# openSX70_MEROE_V7-5_20190606.net
KiCad netlist of a schematic drawn in EAGLE
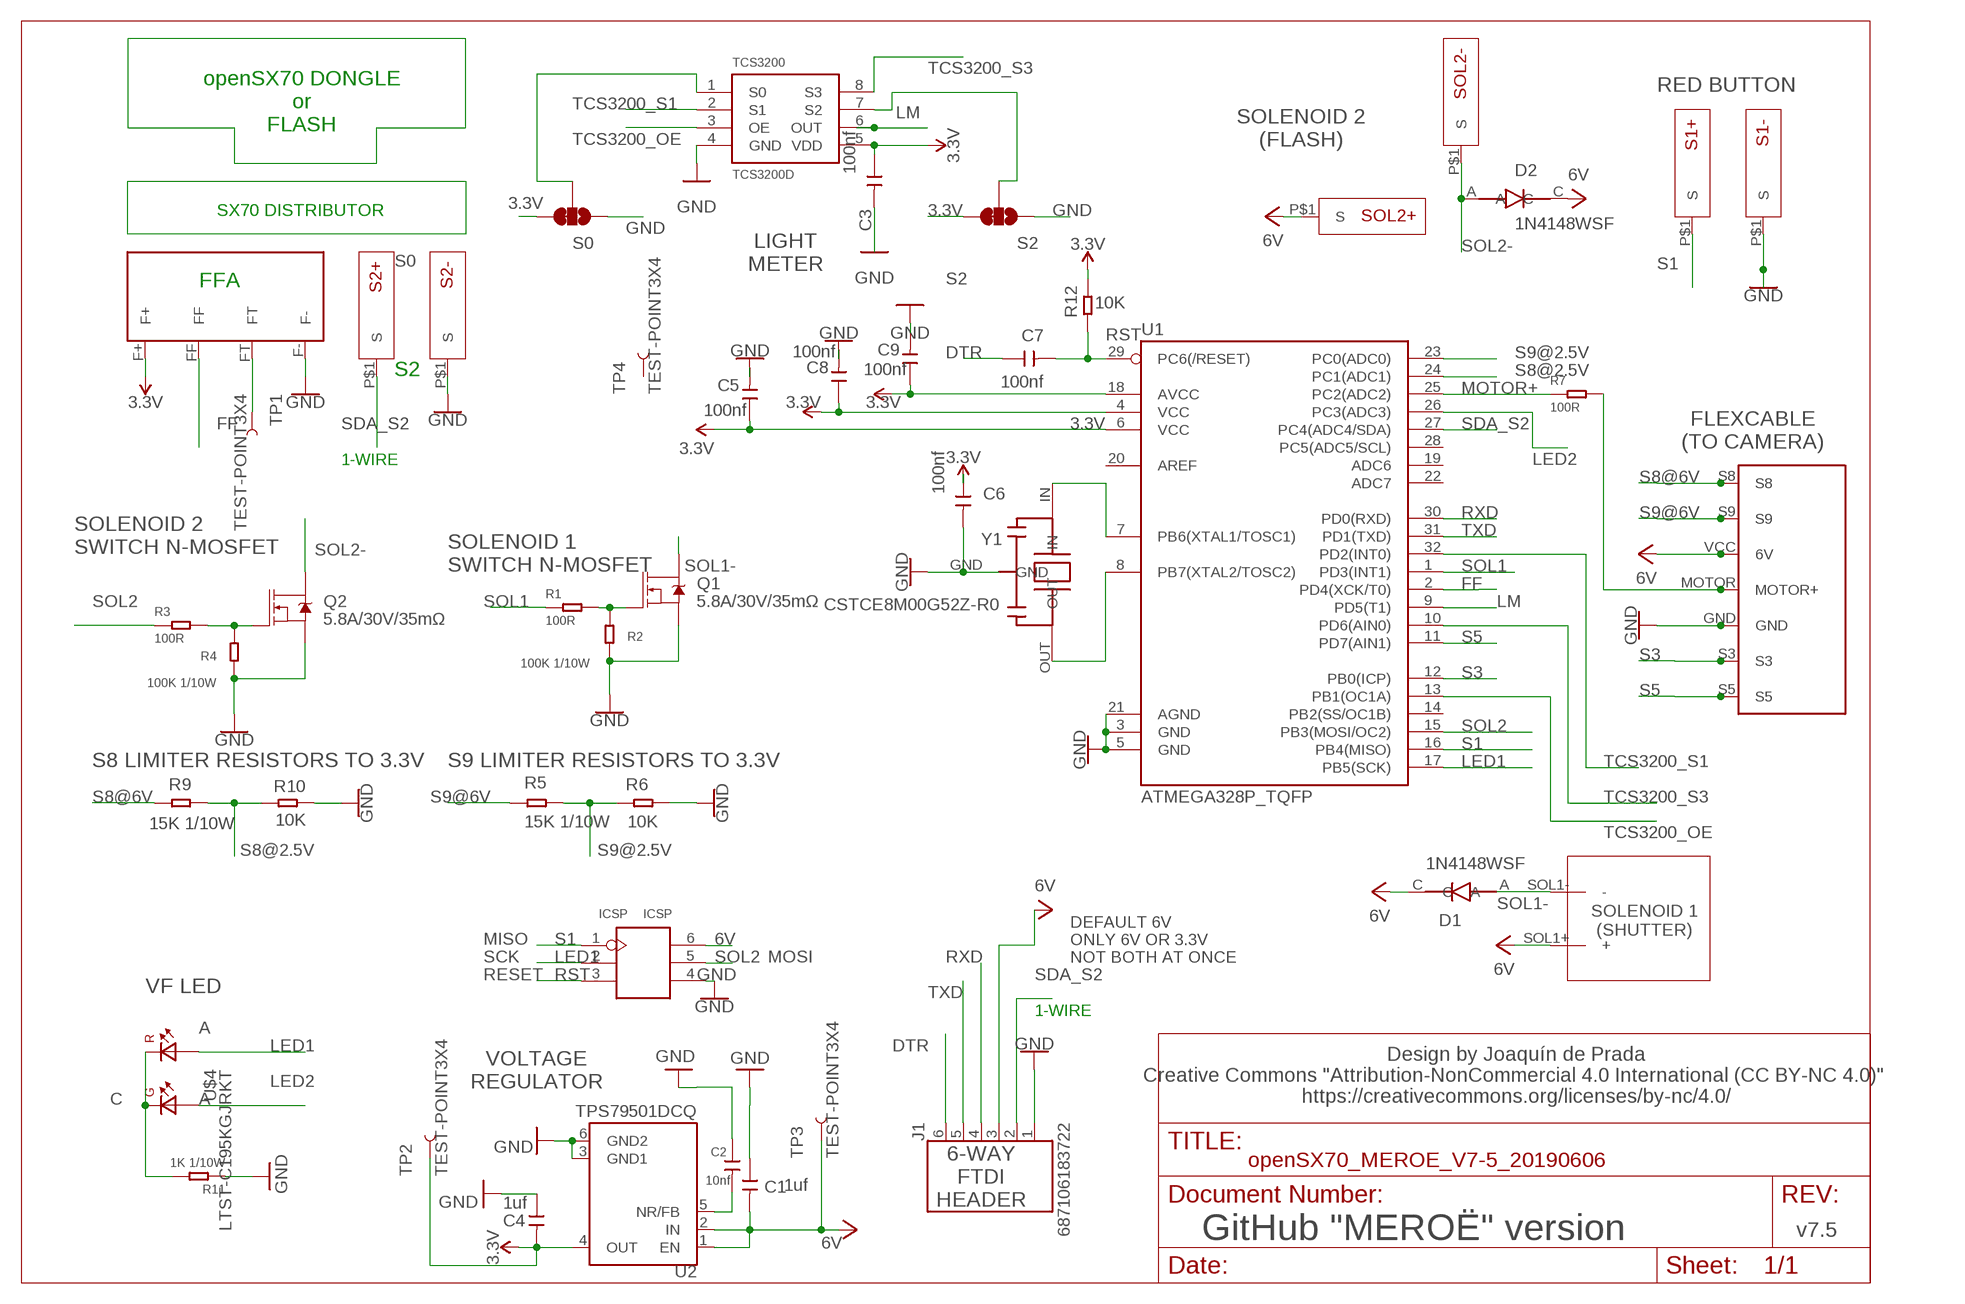
[diagram p0: schematic, sheet 1]

(export (version "E")
  (design (tool "Eeschema 10.0.6"))
  (components
    (comp (ref "C1")
      (value "1uf")
      (footprint "eagle-import:C0603")
      (fields (field (name "MPN") "CC0603KRX5R6BB106"))
      (libsource (lib "eagle-import") (part "CERAMIC-10UF-10V-10%-X5R(0603)"))
    )
    (comp (ref "C2")
      (value "10nf")
      (footprint "eagle-import:C0603")
      (fields (field (name "MPN") "CC0603KRX7R9BB104"))
      (libsource (lib "eagle-import") (part "CERAMIC-100NF-50V-10%-X7R(0603)"))
    )
    (comp (ref "C3")
      (value "100nf")
      (footprint "eagle-import:C0603")
      (fields (field (name "MPN") "CC0603KRX7R9BB104"))
      (libsource (lib "eagle-import") (part "CERAMIC-100NF-50V-10%-X7R(0603)"))
    )
    (comp (ref "C4")
      (value "1uf")
      (footprint "eagle-import:C0603")
      (fields (field (name "MPN") "CC0603KRX5R6BB106"))
      (libsource (lib "eagle-import") (part "CERAMIC-10UF-10V-10%-X5R(0603)"))
    )
    (comp (ref "C5")
      (value "100nf")
      (footprint "eagle-import:C0603")
      (fields (field (name "MPN") "CC0603KRX7R9BB104"))
      (libsource (lib "eagle-import") (part "CERAMIC-100NF-50V-10%-X7R(0603)"))
    )
    (comp (ref "C6")
      (value "100nf")
      (footprint "eagle-import:C0603")
      (fields (field (name "MPN") "CC0603KRX7R9BB104"))
      (libsource (lib "eagle-import") (part "CERAMIC-100NF-50V-10%-X7R(0603)"))
    )
    (comp (ref "C7")
      (value "100nf")
      (footprint "eagle-import:C0603")
      (fields (field (name "MPN") "CC0603KRX7R9BB104"))
      (libsource (lib "eagle-import") (part "CERAMIC-100NF-50V-10%-X7R(0603)"))
    )
    (comp (ref "C8")
      (value "100nf")
      (footprint "eagle-import:C0603")
      (fields (field (name "MPN") "CC0603KRX7R9BB104"))
      (libsource (lib "eagle-import") (part "CERAMIC-100NF-50V-10%-X7R(0603)"))
    )
    (comp (ref "C9")
      (value "100nf")
      (footprint "eagle-import:C0603")
      (fields (field (name "MPN") "CC0603KRX7R9BB104"))
      (libsource (lib "eagle-import") (part "CERAMIC-100NF-50V-10%-X7R(0603)"))
    )
    (comp (ref "D1")
      (value "1N4148WSF")
      (footprint "eagle-import:SODFL2512X100N")
      (fields (field (name "MANUFACTURER") "Fairchild Semiconductor"))
      (libsource (lib "eagle-import") (part "1N4148WS"))
    )
    (comp (ref "D2")
      (value "1N4148WSF")
      (footprint "eagle-import:SODFL2512X100N")
      (fields (field (name "MANUFACTURER") "Fairchild Semiconductor"))
      (libsource (lib "eagle-import") (part "1N4148WS"))
    )
    (comp (ref "ICSP")
      (value "ICSP")
      (footprint "eagle-import:H2X3-2.54")
      (libsource (lib "eagle-import") (part "ICSP"))
    )
    (comp (ref "J1")
      (value "687106183722")
      (footprint "eagle-import:687106183722")
      (fields (field (name "MF") "Wurth Electronics"))
      (libsource (lib "eagle-import") (part "687106183722"))
    )
    (comp (ref "Q1")
      (value "5.8A/30V/35mΩ")
      (footprint "eagle-import:SOT23-3")
      (libsource (lib "eagle-import") (part "MOSFET-NCH-AO3404A"))
    )
    (comp (ref "Q2")
      (value "5.8A/30V/35mΩ")
      (footprint "eagle-import:SOT23-3")
      (libsource (lib "eagle-import") (part "MOSFET-NCH-AO3404A"))
    )
    (comp (ref "R1")
      (value "100R")
      (footprint "eagle-import:R0603")
      (fields (field (name "MPN") "RC0603JR-07100RL"))
      (libsource (lib "eagle-import") (part "SMD-RES-100R-5%-1/10W(0603)"))
    )
    (comp (ref "R2")
      (value "100K 1/10W")
      (footprint "eagle-import:R0603")
      (fields (field (name "MPN") "RC0603JR-07100KL"))
      (libsource (lib "eagle-import") (part "SMD-RES-100K-5%-1/10W(0603)"))
    )
    (comp (ref "R3")
      (value "100R")
      (footprint "eagle-import:R0603")
      (fields (field (name "MPN") "RC0603JR-07100RL"))
      (libsource (lib "eagle-import") (part "SMD-RES-100R-5%-1/10W(0603)"))
    )
    (comp (ref "R4")
      (value "100K 1/10W")
      (footprint "eagle-import:R0603")
      (fields (field (name "MPN") "RC0603JR-07100KL"))
      (libsource (lib "eagle-import") (part "SMD-RES-100K-5%-1/10W(0603)"))
    )
    (comp (ref "R5")
      (value "15K 1/10W")
      (footprint "eagle-import:R0603")
      (fields (field (name "MPN") "RC0603FR-0715KL"))
      (libsource (lib "eagle-import") (part "SMD-RES-15K-1%-1/10W(0603)"))
    )
    (comp (ref "R6")
      (value "10K")
      (footprint "eagle-import:R0603")
      (fields (field (name "MPN") "RC0603FR-0710KL"))
      (libsource (lib "eagle-import") (part "SMD-RES-10K-1%-1/10W(0603)"))
    )
    (comp (ref "R7")
      (value "100R")
      (footprint "eagle-import:R0603")
      (fields (field (name "MPN") "RC0603JR-07100RL"))
      (libsource (lib "eagle-import") (part "SMD-RES-100R-5%-1/10W(0603)"))
    )
    (comp (ref "R9")
      (value "15K 1/10W")
      (footprint "eagle-import:R0603")
      (fields (field (name "MPN") "RC0603FR-0715KL"))
      (libsource (lib "eagle-import") (part "SMD-RES-15K-1%-1/10W(0603)"))
    )
    (comp (ref "R10")
      (value "10K")
      (footprint "eagle-import:R0603")
      (fields (field (name "MPN") "RC0603FR-0710KL"))
      (libsource (lib "eagle-import") (part "SMD-RES-10K-1%-1/10W(0603)"))
    )
    (comp (ref "R11")
      (value "1K 1/10W")
      (footprint "eagle-import:R0603")
      (fields (field (name "MPN") "RC0603JR-071KL"))
      (libsource (lib "eagle-import") (part "SMD-RES-1K-5%-1/10W(0603)"))
    )
    (comp (ref "R12")
      (value "10K")
      (footprint "eagle-import:R0603")
      (fields (field (name "MPN") "RC0603FR-0710KL"))
      (libsource (lib "eagle-import") (part "SMD-RES-10K-1%-1/10W(0603)"))
    )
    (comp (ref "S0")
      (value "S0")
      (footprint "eagle-import:SMT-JUMPER_3_1-NC_TRACE_SILK")
      (libsource (lib "eagle-import") (part "JUMPER-SMT_3_1-NC_TRACE_SILK"))
    )
    (comp (ref "S1+")
      (value "SX70-S-PAD-NEW")
      (footprint "eagle-import:SX70-S-PAD2")
      (libsource (lib "eagle-import") (part "SX70-S-PAD-NEW"))
    )
    (comp (ref "S1-")
      (value "SX70-S-PAD-NEW")
      (footprint "eagle-import:SX70-S-PAD2")
      (libsource (lib "eagle-import") (part "SX70-S-PAD-NEW"))
    )
    (comp (ref "S2")
      (value "S2")
      (footprint "eagle-import:SMT-JUMPER_3_1-NC_TRACE_SILK")
      (libsource (lib "eagle-import") (part "JUMPER-SMT_3_1-NC_TRACE_SILK"))
    )
    (comp (ref "S2+")
      (value "SX70-S-PAD-NEW")
      (footprint "eagle-import:SX70-S-PAD2")
      (libsource (lib "eagle-import") (part "SX70-S-PAD-NEW"))
    )
    (comp (ref "S2-")
      (value "SX70-S-PAD-NEW")
      (footprint "eagle-import:SX70-S-PAD2")
      (libsource (lib "eagle-import") (part "SX70-S-PAD-NEW"))
    )
    (comp (ref "SOL1")
      (value "SX70-SOLENOID1-2PADS")
      (footprint "eagle-import:SX70-SOLENOID1-2")
      (libsource (lib "eagle-import") (part "SX70-SOLENOID1-2PADS"))
    )
    (comp (ref "SOL2+")
      (value "SX70-S-PAD-NEW")
      (footprint "eagle-import:SX70-S-PAD2")
      (libsource (lib "eagle-import") (part "SX70-S-PAD-NEW"))
    )
    (comp (ref "SOL2-")
      (value "SX70-S-PAD-NEW")
      (footprint "eagle-import:SX70-S-PAD2")
      (libsource (lib "eagle-import") (part "SX70-S-PAD-NEW"))
    )
    (comp (ref "TCS3200")
      (value "TCS3200D")
      (footprint "eagle-import:SOIC8")
      (fields (field (name "MF") "ams") (field (name "MP") "TCS3200D-TR"))
      (libsource (lib "eagle-import") (part "TCS3200D"))
    )
    (comp (ref "TP1")
      (value "TEST-POINT3X4")
      (footprint "eagle-import:PAD.03X.04")
      (libsource (lib "eagle-import") (part "TEST-POINT3X4"))
    )
    (comp (ref "TP2")
      (value "TEST-POINT3X4")
      (footprint "eagle-import:PAD.03X.04")
      (libsource (lib "eagle-import") (part "TEST-POINT3X4"))
    )
    (comp (ref "TP3")
      (value "TEST-POINT3X4")
      (footprint "eagle-import:PAD.03X.04")
      (libsource (lib "eagle-import") (part "TEST-POINT3X4"))
    )
    (comp (ref "TP4")
      (value "TEST-POINT3X4")
      (footprint "eagle-import:PAD.03X.04")
      (libsource (lib "eagle-import") (part "TEST-POINT3X4"))
    )
    (comp (ref "U$1")
      (value "SX70-7-PAD")
      (footprint "eagle-import:SX70-7-PAD-PROPER")
      (libsource (lib "eagle-import") (part "SX70-7-PAD"))
    )
    (comp (ref "U$2")
      (value "FFA")
      (footprint "eagle-import:FFA-PAD-PACKAGE")
      (libsource (lib "eagle-import") (part "SX70-FFA-PAD"))
    )
    (comp (ref "U$4")
      (value "LTST-C195KGJRKT")
      (footprint "eagle-import:LTST-BILED-15X16")
      (fields (field (name "MF") "Lite-On Inc."))
      (libsource (lib "eagle-import") (part "LTST-C195KGJRKT"))
    )
    (comp (ref "U1")
      (value "ATMEGA328P_TQFP")
      (footprint "eagle-import:TQFP32-08")
      (libsource (lib "eagle-import") (part "ATMEGA328P_TQFP"))
    )
    (comp (ref "U2")
      (value "TPS79501DCQ")
      (footprint "eagle-import:SOT127P706X180-6N")
      (fields (field (name "MF") "Texas Instruments"))
      (libsource (lib "eagle-import") (part "TPS79501DCQ"))
    )
    (comp (ref "Y1")
      (value "CSTCE8M00G52Z-R0")
      (footprint "eagle-import:CFP95P160X100-3N")
      (fields (field (name "MF") "Murata") (field (name "MP") "CSTCE16M0V53-R0"))
      (libsource (lib "eagle-import") (part "CSTCE16M0V53-R0"))
    )
  )
  (nets
    (net (code "1") (name "/DTR") (class "Default")
      (node (ref "C7") (pin "1") (pinfunction "1_1") (pintype "passive"))
      (node (ref "J1") (pin "6") (pinfunction "1_6") (pintype "passive"))
    )
    (net (code "2") (name "/FF") (class "Default")
      (node (ref "U$2") (pin "FF") (pinfunction "FF_FF") (pintype "bidirectional"))
      (node (ref "U1") (pin "2") (pinfunction "PD4(XCK/T0)_2") (pintype "bidirectional"))
    )
    (net (code "3") (name "/LED1") (class "Default")
      (node (ref "ICSP") (pin "2") (pinfunction "SCK_2") (pintype "bidirectional"))
      (node (ref "U$4") (pin "P$2") (pinfunction "A2_P$2") (pintype "passive"))
      (node (ref "U1") (pin "17") (pinfunction "PB5(SCK)_17") (pintype "bidirectional"))
    )
    (net (code "4") (name "/LED2") (class "Default")
      (node (ref "U$4") (pin "P$1") (pinfunction "A1_P$1") (pintype "passive"))
      (node (ref "U1") (pin "26") (pinfunction "PC3(ADC3)_26") (pintype "bidirectional"))
    )
    (net (code "5") (name "/LM") (class "Default")
      (node (ref "TCS3200") (pin "6") (pinfunction "OUT_6") (pintype "bidirectional"))
      (node (ref "U1") (pin "9") (pinfunction "PD5(T1)_9") (pintype "bidirectional"))
    )
    (net (code "6") (name "/MOTOR+") (class "Default")
      (node (ref "R7") (pin "1") (pinfunction "1_1") (pintype "passive"))
      (node (ref "U1") (pin "25") (pinfunction "PC2(ADC2)_25") (pintype "bidirectional"))
    )
    (net (code "7") (name "/RST") (class "Default")
      (node (ref "C7") (pin "2") (pinfunction "2_2") (pintype "passive"))
      (node (ref "ICSP") (pin "3") (pinfunction "RST_3") (pintype "bidirectional"))
      (node (ref "R12") (pin "1") (pinfunction "1_1") (pintype "passive"))
      (node (ref "U1") (pin "29") (pinfunction "PC6(/RESET)_29") (pintype "bidirectional"))
    )
    (net (code "8") (name "/RXD") (class "Default")
      (node (ref "J1") (pin "4") (pinfunction "3_4") (pintype "passive"))
      (node (ref "U1") (pin "30") (pinfunction "PD0(RXD)_30") (pintype "bidirectional"))
    )
    (net (code "9") (name "/S1") (class "Default")
      (node (ref "ICSP") (pin "1") (pinfunction "MISO_1") (pintype "bidirectional"))
      (node (ref "S1+") (pin "P$1") (pinfunction "S_P$1") (pintype "bidirectional"))
      (node (ref "U1") (pin "16") (pinfunction "PB4(MISO)_16") (pintype "bidirectional"))
    )
    (net (code "10") (name "/S3") (class "Default")
      (node (ref "U$1") (pin "S3") (pinfunction "S3_S3") (pintype "bidirectional"))
      (node (ref "U1") (pin "12") (pinfunction "PB0(ICP)_12") (pintype "bidirectional"))
    )
    (net (code "11") (name "/S5") (class "Default")
      (node (ref "U$1") (pin "S5") (pinfunction "S5_S5") (pintype "bidirectional"))
      (node (ref "U1") (pin "11") (pinfunction "PD7(AIN1)_11") (pintype "bidirectional"))
    )
    (net (code "12") (name "/S8@2.5V") (class "Default")
      (node (ref "R10") (pin "1") (pinfunction "1_1") (pintype "passive"))
      (node (ref "R9") (pin "2") (pinfunction "2_2") (pintype "passive"))
      (node (ref "U1") (pin "24") (pinfunction "PC1(ADC1)_24") (pintype "bidirectional"))
    )
    (net (code "13") (name "/S8@6V") (class "Default")
      (node (ref "R9") (pin "1") (pinfunction "1_1") (pintype "passive"))
      (node (ref "U$1") (pin "S8") (pinfunction "S8_S8") (pintype "bidirectional"))
    )
    (net (code "14") (name "/S9@2.5V") (class "Default")
      (node (ref "R5") (pin "2") (pinfunction "2_2") (pintype "passive"))
      (node (ref "R6") (pin "1") (pinfunction "1_1") (pintype "passive"))
      (node (ref "U1") (pin "23") (pinfunction "PC0(ADC0)_23") (pintype "bidirectional"))
    )
    (net (code "15") (name "/S9@6V") (class "Default")
      (node (ref "R5") (pin "1") (pinfunction "1_1") (pintype "passive"))
      (node (ref "U$1") (pin "S9") (pinfunction "S9_S9") (pintype "bidirectional"))
    )
    (net (code "16") (name "/SDA_S2") (class "Default")
      (node (ref "J1") (pin "2") (pinfunction "5_2") (pintype "passive"))
      (node (ref "S2+") (pin "P$1") (pinfunction "S_P$1") (pintype "bidirectional"))
      (node (ref "U1") (pin "27") (pinfunction "PC4(ADC4/SDA)_27") (pintype "bidirectional"))
    )
    (net (code "17") (name "/SOL1") (class "Default")
      (node (ref "R1") (pin "1") (pinfunction "1_1") (pintype "passive"))
      (node (ref "U1") (pin "1") (pinfunction "PD3(INT1)_1") (pintype "bidirectional"))
    )
    (net (code "18") (name "/SOL1-") (class "Default")
      (node (ref "D1") (pin "A") (pinfunction "A_A") (pintype "passive"))
      (node (ref "Q1") (pin "3") (pinfunction "D_3") (pintype "bidirectional"))
      (node (ref "SOL1") (pin "SOL1-") (pinfunction "-_SOL1-") (pintype "bidirectional"))
    )
    (net (code "19") (name "/SOL2") (class "Default")
      (node (ref "ICSP") (pin "5") (pinfunction "MOSI_5") (pintype "bidirectional"))
      (node (ref "R3") (pin "1") (pinfunction "1_1") (pintype "passive"))
      (node (ref "U1") (pin "15") (pinfunction "PB3(MOSI/OC2)_15") (pintype "bidirectional"))
    )
    (net (code "20") (name "/SOL2-") (class "Default")
      (node (ref "D2") (pin "A") (pinfunction "A_A") (pintype "passive"))
      (node (ref "Q2") (pin "3") (pinfunction "D_3") (pintype "bidirectional"))
      (node (ref "SOL2-") (pin "P$1") (pinfunction "S_P$1") (pintype "bidirectional"))
    )
    (net (code "21") (name "/TCS3200_OE") (class "Default")
      (node (ref "TCS3200") (pin "3") (pinfunction "OE_3") (pintype "bidirectional"))
      (node (ref "U1") (pin "13") (pinfunction "PB1(OC1A)_13") (pintype "bidirectional"))
    )
    (net (code "22") (name "/TCS3200_S1") (class "Default")
      (node (ref "TCS3200") (pin "2") (pinfunction "S1_2") (pintype "bidirectional"))
      (node (ref "U1") (pin "32") (pinfunction "PD2(INT0)_32") (pintype "bidirectional"))
    )
    (net (code "23") (name "/TCS3200_S3") (class "Default")
      (node (ref "TCS3200") (pin "8") (pinfunction "S3_8") (pintype "bidirectional"))
      (node (ref "U1") (pin "10") (pinfunction "PD6(AIN0)_10") (pintype "bidirectional"))
    )
    (net (code "24") (name "/TXD") (class "Default")
      (node (ref "J1") (pin "5") (pinfunction "2_5") (pintype "passive"))
      (node (ref "U1") (pin "31") (pinfunction "PD1(TXD)_31") (pintype "bidirectional"))
    )
    (net (code "25") (name "3.3V") (class "Default")
      (node (ref "C3") (pin "1") (pinfunction "1_1") (pintype "passive"))
      (node (ref "C4") (pin "2") (pinfunction "2_2") (pintype "passive"))
      (node (ref "C5") (pin "1") (pinfunction "1_1") (pintype "passive"))
      (node (ref "C6") (pin "1") (pinfunction "1_1") (pintype "passive"))
      (node (ref "C8") (pin "1") (pinfunction "1_1") (pintype "passive"))
      (node (ref "C9") (pin "1") (pinfunction "1_1") (pintype "passive"))
      (node (ref "R12") (pin "2") (pinfunction "2_2") (pintype "passive"))
      (node (ref "S0") (pin "3") (pinfunction "3_3") (pintype "passive"))
      (node (ref "S2") (pin "3") (pinfunction "3_3") (pintype "passive"))
      (node (ref "TCS3200") (pin "5") (pinfunction "VDD_5") (pintype "bidirectional"))
      (node (ref "TP2") (pin "P$1") (pinfunction "1_P$1") (pintype "bidirectional"))
      (node (ref "U$2") (pin "F+") (pinfunction "F+_F+") (pintype "bidirectional"))
      (node (ref "U1") (pin "18") (pinfunction "AVCC_18") (pintype "bidirectional"))
      (node (ref "U1") (pin "4") (pinfunction "VCC_4") (pintype "bidirectional"))
      (node (ref "U1") (pin "6") (pinfunction "VCC_6") (pintype "bidirectional"))
      (node (ref "U2") (pin "4") (pinfunction "OUT_4") (pintype "output"))
    )
    (net (code "26") (name "6V") (class "Default")
      (node (ref "C1") (pin "2") (pinfunction "2_2") (pintype "passive"))
      (node (ref "D1") (pin "C") (pinfunction "C_C") (pintype "passive"))
      (node (ref "D2") (pin "C") (pinfunction "C_C") (pintype "passive"))
      (node (ref "ICSP") (pin "6") (pinfunction "VCC_6") (pintype "bidirectional"))
      (node (ref "J1") (pin "3") (pinfunction "4_3") (pintype "passive"))
      (node (ref "SOL1") (pin "SOL1+") (pinfunction "+_SOL1+") (pintype "bidirectional"))
      (node (ref "SOL2+") (pin "P$1") (pinfunction "S_P$1") (pintype "bidirectional"))
      (node (ref "TP3") (pin "P$1") (pinfunction "1_P$1") (pintype "bidirectional"))
      (node (ref "U$1") (pin "VCC") (pinfunction "6V_VCC") (pintype "bidirectional"))
      (node (ref "U2") (pin "1") (pinfunction "EN_1") (pintype "input"))
      (node (ref "U2") (pin "2") (pinfunction "IN_2") (pintype "input"))
    )
    (net (code "27") (name "GND") (class "Default")
      (node (ref "C1") (pin "1") (pinfunction "1_1") (pintype "passive"))
      (node (ref "C2") (pin "1") (pinfunction "1_1") (pintype "passive"))
      (node (ref "C3") (pin "2") (pinfunction "2_2") (pintype "passive"))
      (node (ref "C4") (pin "1") (pinfunction "1_1") (pintype "passive"))
      (node (ref "C5") (pin "2") (pinfunction "2_2") (pintype "passive"))
      (node (ref "C6") (pin "2") (pinfunction "2_2") (pintype "passive"))
      (node (ref "C8") (pin "2") (pinfunction "2_2") (pintype "passive"))
      (node (ref "C9") (pin "2") (pinfunction "2_2") (pintype "passive"))
      (node (ref "ICSP") (pin "4") (pinfunction "GND_4") (pintype "bidirectional"))
      (node (ref "J1") (pin "1") (pinfunction "6_1") (pintype "passive"))
      (node (ref "Q1") (pin "2") (pinfunction "S_2") (pintype "bidirectional"))
      (node (ref "Q2") (pin "2") (pinfunction "S_2") (pintype "bidirectional"))
      (node (ref "R10") (pin "2") (pinfunction "2_2") (pintype "passive"))
      (node (ref "R11") (pin "1") (pinfunction "1_1") (pintype "passive"))
      (node (ref "R2") (pin "1") (pinfunction "1_1") (pintype "passive"))
      (node (ref "R4") (pin "1") (pinfunction "1_1") (pintype "passive"))
      (node (ref "R6") (pin "2") (pinfunction "2_2") (pintype "passive"))
      (node (ref "S0") (pin "1") (pinfunction "1_1") (pintype "passive"))
      (node (ref "S1-") (pin "P$1") (pinfunction "S_P$1") (pintype "bidirectional"))
      (node (ref "S2") (pin "1") (pinfunction "1_1") (pintype "passive"))
      (node (ref "S2-") (pin "P$1") (pinfunction "S_P$1") (pintype "bidirectional"))
      (node (ref "TCS3200") (pin "4") (pinfunction "GND_4") (pintype "bidirectional"))
      (node (ref "U$1") (pin "GND") (pinfunction "GND_GND") (pintype "bidirectional"))
      (node (ref "U$2") (pin "F-") (pinfunction "F-_F-") (pintype "bidirectional"))
      (node (ref "U1") (pin "21") (pinfunction "AGND_21") (pintype "bidirectional"))
      (node (ref "U1") (pin "3") (pinfunction "GND_3") (pintype "bidirectional"))
      (node (ref "U1") (pin "5") (pinfunction "GND_5") (pintype "bidirectional"))
      (node (ref "U2") (pin "3") (pinfunction "GND1_3") (pintype "power_in"))
      (node (ref "U2") (pin "6") (pinfunction "GND2_6") (pintype "power_in"))
      (node (ref "Y1") (pin "GND") (pinfunction "GND_GND") (pintype "passive"))
    )
    (net (code "28") (name "Net-(Q1-G)") (class "Default")
      (node (ref "Q1") (pin "1") (pinfunction "G_1") (pintype "bidirectional"))
      (node (ref "R1") (pin "2") (pinfunction "2_2") (pintype "passive"))
      (node (ref "R2") (pin "2") (pinfunction "2_2") (pintype "passive"))
    )
    (net (code "29") (name "Net-(Q2-G)") (class "Default")
      (node (ref "Q2") (pin "1") (pinfunction "G_1") (pintype "bidirectional"))
      (node (ref "R3") (pin "2") (pinfunction "2_2") (pintype "passive"))
      (node (ref "R4") (pin "2") (pinfunction "2_2") (pintype "passive"))
    )
    (net (code "30") (name "Net-(TCS3200-S0)") (class "Default")
      (node (ref "S0") (pin "2") (pinfunction "2_2") (pintype "passive"))
      (node (ref "TCS3200") (pin "1") (pinfunction "S0_1") (pintype "bidirectional"))
    )
    (net (code "31") (name "Net-(TCS3200-S2)") (class "Default")
      (node (ref "S2") (pin "2") (pinfunction "2_2") (pintype "passive"))
      (node (ref "TCS3200") (pin "7") (pinfunction "S2_7") (pintype "bidirectional"))
    )
    (net (code "32") (name "Net-(TP1-1)") (class "Default")
      (node (ref "TP1") (pin "P$1") (pinfunction "1_P$1") (pintype "bidirectional"))
      (node (ref "U$2") (pin "FT") (pinfunction "FT_FT") (pintype "bidirectional"))
    )
    (net (code "33") (name "Net-(U$1-MOTOR+)") (class "Default")
      (node (ref "R7") (pin "2") (pinfunction "2_2") (pintype "passive"))
      (node (ref "U$1") (pin "MOTOR") (pinfunction "MOTOR+_MOTOR") (pintype "bidirectional"))
    )
    (net (code "34") (name "Net-(U$4-K1)") (class "Default")
      (node (ref "R11") (pin "2") (pinfunction "2_2") (pintype "passive"))
      (node (ref "U$4") (pin "P$3") (pinfunction "K1_P$3") (pintype "passive"))
      (node (ref "U$4") (pin "P$4") (pinfunction "K2_P$4") (pintype "passive"))
    )
    (net (code "35") (name "Net-(U1-PB6(XTAL1{slash}TOSC1))") (class "Default")
      (node (ref "U1") (pin "7") (pinfunction "PB6(XTAL1/TOSC1)_7") (pintype "bidirectional"))
      (node (ref "Y1") (pin "IN") (pinfunction "IN_IN") (pintype "input"))
    )
    (net (code "36") (name "Net-(U1-PB7(XTAL2{slash}TOSC2))") (class "Default")
      (node (ref "U1") (pin "8") (pinfunction "PB7(XTAL2/TOSC2)_8") (pintype "bidirectional"))
      (node (ref "Y1") (pin "OUT") (pinfunction "OUT_OUT") (pintype "output"))
    )
    (net (code "37") (name "Net-(U2-NR{slash}FB)") (class "Default")
      (node (ref "C2") (pin "2") (pinfunction "2_2") (pintype "passive"))
      (node (ref "U2") (pin "5") (pinfunction "NR/FB_5") (pintype "input"))
    )
    (net (code "38") (name "unconnected-(TP4-1-PadP$1)") (class "Default")
      (node (ref "TP4") (pin "P$1") (pinfunction "1_P$1") (pintype "bidirectional"))
    )
    (net (code "39") (name "unconnected-(U1-ADC6-Pad19)") (class "Default")
      (node (ref "U1") (pin "19") (pinfunction "ADC6_19") (pintype "bidirectional"))
    )
    (net (code "40") (name "unconnected-(U1-ADC7-Pad22)") (class "Default")
      (node (ref "U1") (pin "22") (pinfunction "ADC7_22") (pintype "bidirectional"))
    )
    (net (code "41") (name "unconnected-(U1-AREF-Pad20)") (class "Default")
      (node (ref "U1") (pin "20") (pinfunction "AREF_20") (pintype "bidirectional"))
    )
    (net (code "42") (name "unconnected-(U1-PB2(SS{slash}OC1B)-Pad14)") (class "Default")
      (node (ref "U1") (pin "14") (pinfunction "PB2(SS/OC1B)_14") (pintype "bidirectional"))
    )
    (net (code "43") (name "unconnected-(U1-PC5(ADC5{slash}SCL)-Pad28)") (class "Default")
      (node (ref "U1") (pin "28") (pinfunction "PC5(ADC5/SCL)_28") (pintype "bidirectional"))
    )
  )
)
